# PG4_SHEET2.net
KiCad netlist of a schematic drawn in Altium Designer
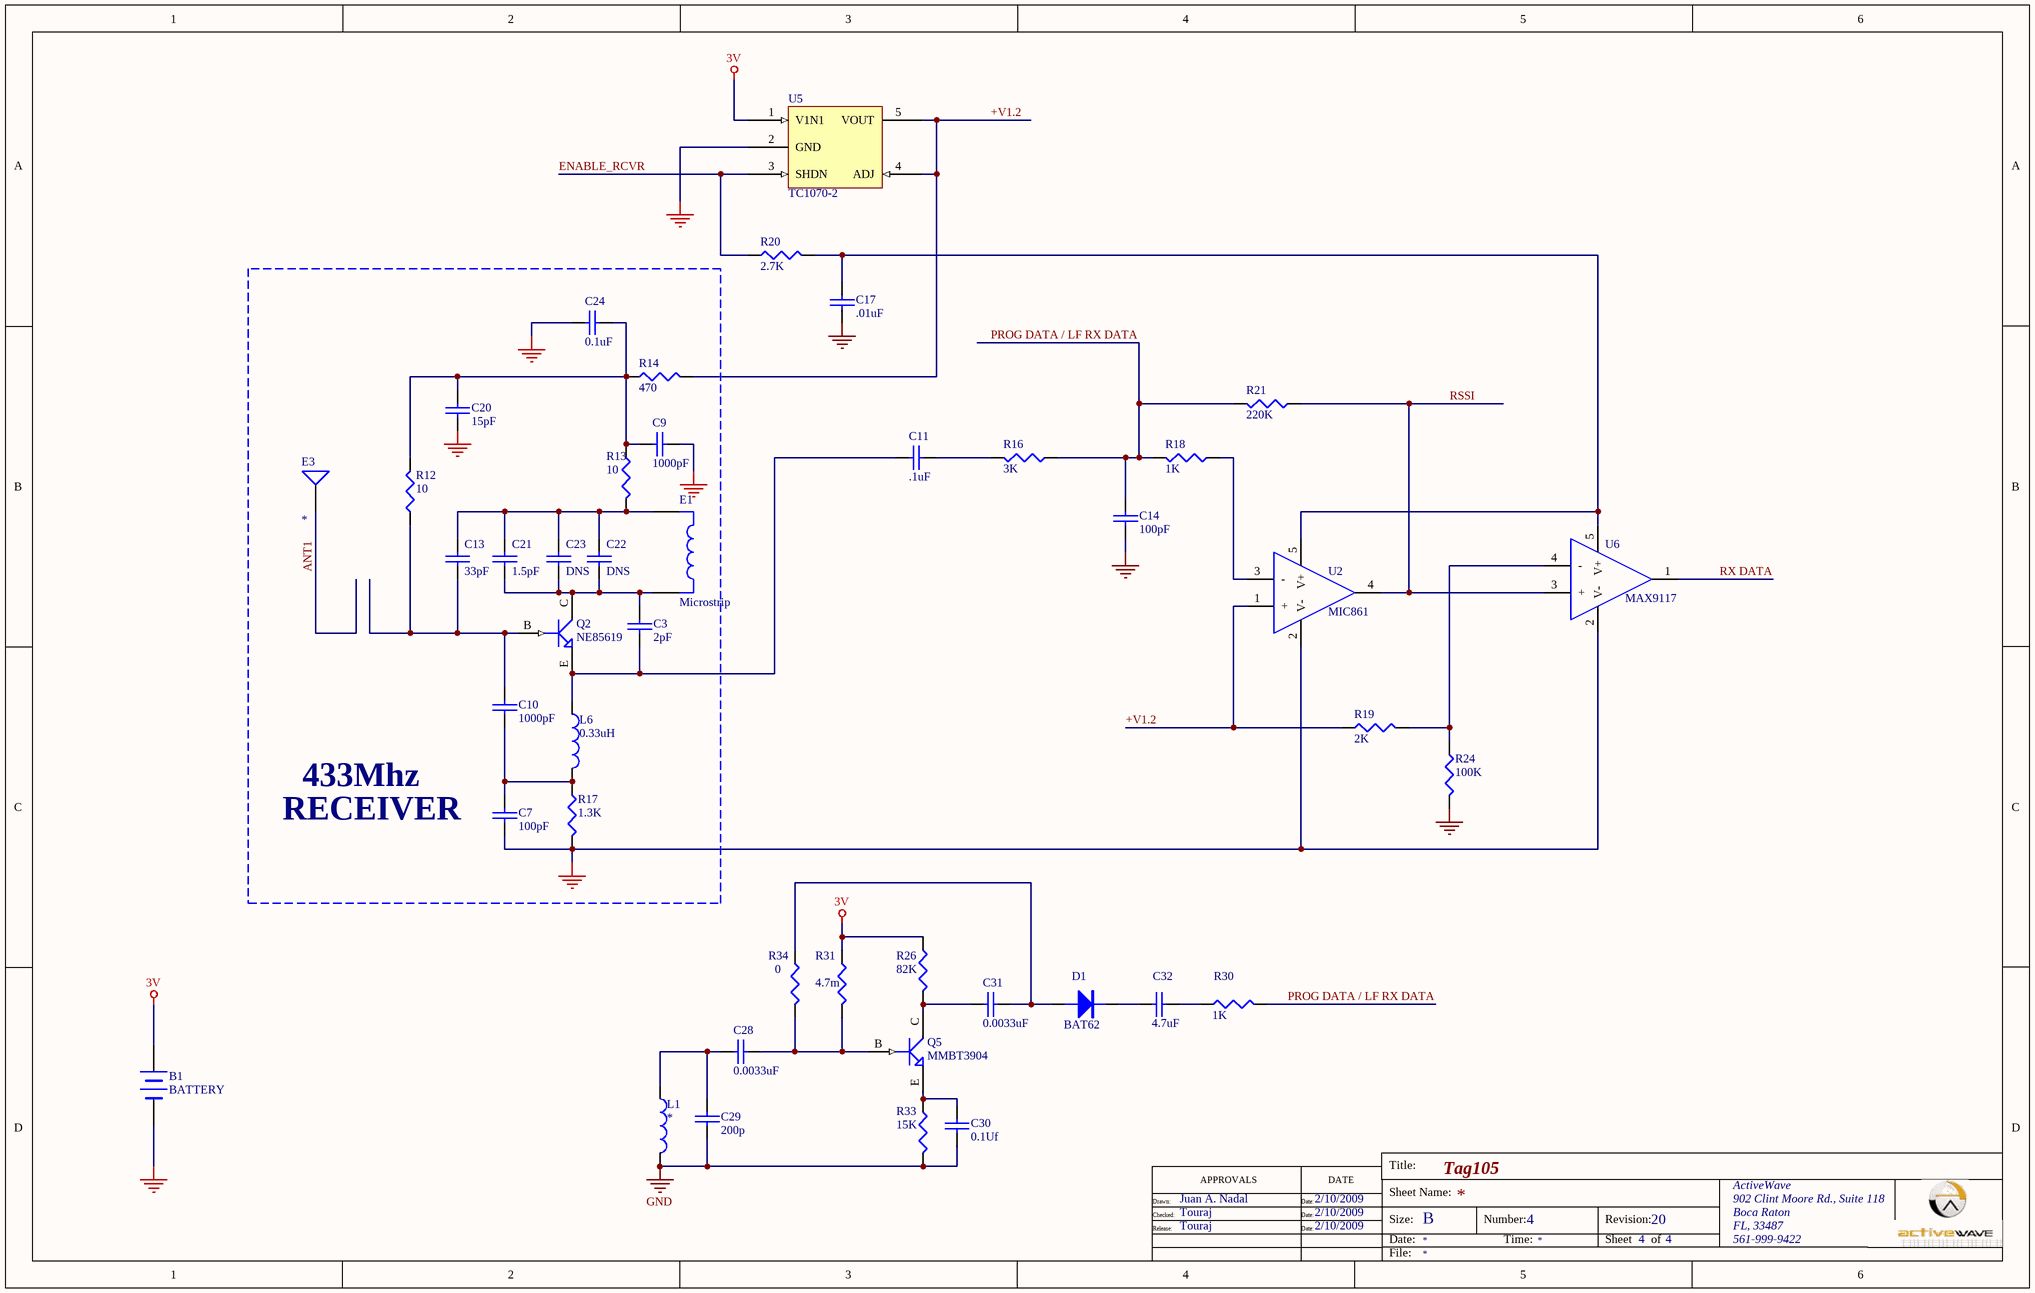
[diagram p0: PG4 SHEET2.schdoc]

(export (version "E")
  (design (tool "Eeschema 10.0.6"))
  (components
    (comp (ref "B1")
      (value "BATTERY")
      (footprint "BATT HOLDER COIN CR2032 CUT")
      (description "Battery")
      (libsource (lib "ActiveWave MasterLib") (part "BATTERY"))
    )
    (comp (ref "C3")
      (value "2pF")
      (footprint "0603")
      (description "Capacitor")
      (libsource (lib "ActiveWave MasterLib") (part "CAP-0603"))
    )
    (comp (ref "C7")
      (value "100pF")
      (footprint "0603")
      (description "Capacitor")
      (libsource (lib "ActiveWave MasterLib") (part "CAP-0603"))
    )
    (comp (ref "C9")
      (value "1000pF")
      (footprint "0603")
      (description "Capacitor")
      (libsource (lib "ActiveWave MasterLib") (part "CAP-0603"))
    )
    (comp (ref "C10")
      (value "1000pF")
      (footprint "0603")
      (description "Capacitor")
      (libsource (lib "ActiveWave MasterLib") (part "CAP-0603"))
    )
    (comp (ref "C11")
      (value ".1uF")
      (footprint "0603")
      (description "Capacitor")
      (libsource (lib "ActiveWave MasterLib") (part "CAP-0603"))
    )
    (comp (ref "C13")
      (value "33pF")
      (footprint "0603")
      (description "Capacitor")
      (libsource (lib "ActiveWave MasterLib") (part "CAP-0603"))
    )
    (comp (ref "C14")
      (value "100pF")
      (footprint "0603")
      (description "Capacitor")
      (libsource (lib "ActiveWave MasterLib") (part "CAP-0603"))
    )
    (comp (ref "C17")
      (value ".01uF")
      (footprint "0603")
      (description "Capacitor")
      (libsource (lib "ActiveWave MasterLib") (part "CAP-0603"))
    )
    (comp (ref "C20")
      (value "15pF")
      (footprint "0603")
      (description "Capacitor")
      (libsource (lib "ActiveWave MasterLib") (part "CAP-0603"))
    )
    (comp (ref "C21")
      (value "1.5pF")
      (footprint "0603")
      (description "Capacitor")
      (libsource (lib "ActiveWave MasterLib") (part "CAP-0603"))
    )
    (comp (ref "C22")
      (value "DNS")
      (footprint "0603")
      (description "Capacitor")
      (libsource (lib "ActiveWave MasterLib") (part "CAP-0603"))
    )
    (comp (ref "C23")
      (value "DNS")
      (footprint "0603")
      (description "Capacitor")
      (libsource (lib "ActiveWave MasterLib") (part "CAP-0603"))
    )
    (comp (ref "C24")
      (value "0.1uF")
      (footprint "0603")
      (description "Capacitor")
      (libsource (lib "ActiveWave MasterLib") (part "CAP-0603"))
    )
    (comp (ref "C28")
      (value "0.0033uF")
      (footprint "0603")
      (description "Capacitor")
      (libsource (lib "ActiveWave MasterLib") (part "CAP-0603"))
    )
    (comp (ref "C29")
      (value "200p")
      (footprint "0603")
      (description "Capacitor")
      (libsource (lib "ActiveWave MasterLib") (part "CAP-0603"))
    )
    (comp (ref "C30")
      (value "0.1Uf")
      (footprint "0603")
      (description "Capacitor")
      (libsource (lib "ActiveWave MasterLib") (part "CAP-0603"))
    )
    (comp (ref "C31")
      (value "0.0033uF")
      (footprint "0603")
      (description "Capacitor")
      (libsource (lib "ActiveWave MasterLib") (part "CAP-0603"))
    )
    (comp (ref "C32")
      (value "4.7uF")
      (footprint "0603")
      (description "Capacitor")
      (libsource (lib "ActiveWave MasterLib") (part "CAP-0603"))
    )
    (comp (ref "D1")
      (value "BAT62")
      (footprint "SMCR_SOD323_V1")
      (libsource (lib "ActiveWave MasterLib") (part "DIODE"))
    )
    (comp (ref "E1")
      (value "Microstrip")
      (footprint "Antenna")
      (fields (field (name "ITEM-DESCRIPTION") "Microstrip"))
      (libsource (lib "ActiveWave MasterLib") (part "ANTENNA"))
    )
    (comp (ref "E3")
      (value "*")
      (footprint "Antenna1")
      (fields (field (name "ALTIUM_VALUE") "*"))
      (libsource (lib "ActiveWave MasterLib") (part "Antenna1"))
    )
    (comp (ref "L1")
      (value "*")
      (footprint "4308RV")
      (fields (field (name "ALTIUM_VALUE") "*"))
      (libsource (lib "ActiveWave MasterLib") (part "INDUCTOR_V1"))
    )
    (comp (ref "L6")
      (value "0.33uH")
      (footprint "0603")
      (libsource (lib "ActiveWave MasterLib") (part "INDUCTOR"))
    )
    (comp (ref "Q2")
      (value "NE85619")
      (footprint "3 PIN ULTRA SUPER MINI MOLD")
      (description "TRANSISTOR NPN 1GHZ SMD")
      (fields (field (name "MANUFACTURER") "??????"))
      (libsource (lib "ActiveWave MasterLib") (part "NE85619"))
    )
    (comp (ref "Q5")
      (value "MMBT3904")
      (footprint "SOT23-EBC")
      (description "NPN SWITCHING TRANSTOR")
      (fields (field (name "MANUFACTURER") "??????"))
      (libsource (lib "ActiveWave MasterLib") (part "MMBT3904"))
    )
    (comp (ref "R12")
      (value "10")
      (footprint "0603")
      (libsource (lib "ActiveWave MasterLib") (part "RES-0603"))
    )
    (comp (ref "R13")
      (value "10")
      (footprint "0603")
      (libsource (lib "ActiveWave MasterLib") (part "RES-0603"))
    )
    (comp (ref "R14")
      (value "470")
      (footprint "0603")
      (libsource (lib "ActiveWave MasterLib") (part "RES-0603"))
    )
    (comp (ref "R16")
      (value "3K")
      (footprint "0603")
      (libsource (lib "ActiveWave MasterLib") (part "RES-0603"))
    )
    (comp (ref "R17")
      (value "1.3K")
      (footprint "0603")
      (libsource (lib "ActiveWave MasterLib") (part "RES-0603"))
    )
    (comp (ref "R18")
      (value "1K")
      (footprint "0603")
      (libsource (lib "ActiveWave MasterLib") (part "RES-0603"))
    )
    (comp (ref "R19")
      (value "2K")
      (footprint "0603")
      (libsource (lib "ActiveWave MasterLib") (part "RES-0603"))
    )
    (comp (ref "R20")
      (value "2.7K")
      (footprint "0603")
      (libsource (lib "ActiveWave MasterLib") (part "RES-0603"))
    )
    (comp (ref "R21")
      (value "220K")
      (footprint "0603")
      (libsource (lib "ActiveWave MasterLib") (part "RES-0603"))
    )
    (comp (ref "R24")
      (value "100K")
      (footprint "0603")
      (libsource (lib "ActiveWave MasterLib") (part "RES-0603"))
    )
    (comp (ref "R26")
      (value "82K")
      (footprint "0603")
      (libsource (lib "ActiveWave MasterLib") (part "RES-0603"))
    )
    (comp (ref "R30")
      (value "1K")
      (footprint "0603")
      (libsource (lib "ActiveWave MasterLib") (part "RES-0603"))
    )
    (comp (ref "R31")
      (value "4.7m")
      (footprint "0603")
      (libsource (lib "ActiveWave MasterLib") (part "RES-0603"))
    )
    (comp (ref "R33")
      (value "15K")
      (footprint "0603")
      (libsource (lib "ActiveWave MasterLib") (part "RES-0603"))
    )
    (comp (ref "R34")
      (value "0")
      (footprint "0603")
      (libsource (lib "ActiveWave MasterLib") (part "RES-0603"))
    )
    (comp (ref "U2")
      (value "MIC861")
      (footprint "SC70")
      (description "Ultra Low Power Op Amp")
      (fields (field (name "MANUFACTURER") "MICREL"))
      (libsource (lib "ActiveWave MasterLib") (part "MIC861BC5"))
    )
    (comp (ref "U5")
      (value "TC1070-2")
      (footprint "SOT23-5A")
      (description "Adjustable CMOS LDOs with Shutdown")
      (fields (field (name "MANUFACTURER") "Microchip Technology"))
      (libsource (lib "ActiveWave MasterLib") (part "TC1070-2"))
    )
    (comp (ref "U6")
      (value "MAX9117")
      (footprint "SC70")
      (description "MAX9117 Comparators")
      (fields (field (name "MANUFACTURER") "MAXIM"))
      (libsource (lib "ActiveWave MasterLib") (part "COMPARATOR MAX9117"))
    )
  )
  (nets
    (net (code "1") (name "/+V1.2") (class "Default")
      (node (ref "R14") (pin "2") (pinfunction "2_2") (pintype "passive"))
      (node (ref "R19") (pin "1") (pinfunction "1_1") (pintype "passive"))
      (node (ref "U2") (pin "1") (pinfunction "+_1") (pintype "passive"))
      (node (ref "U5") (pin "4") (pinfunction "ADJ_4") (pintype "input"))
      (node (ref "U5") (pin "5") (pinfunction "VOUT_5") (pintype "power_in"))
    )
    (net (code "2") (name "/ANT1") (class "Default")
      (node (ref "E3") (pin "1") (pinfunction "1_1") (pintype "passive"))
    )
    (net (code "3") (name "/ENABLE_RCVR") (class "Default")
      (node (ref "R20") (pin "1") (pinfunction "1_1") (pintype "passive"))
      (node (ref "U5") (pin "3") (pinfunction "SHDN_3") (pintype "input"))
    )
    (net (code "4") (name "/PROG DATA {slash} LF RX DATA") (class "Default")
      (node (ref "C14") (pin "2") (pinfunction "2_2") (pintype "passive"))
      (node (ref "R16") (pin "1") (pinfunction "1_1") (pintype "passive"))
      (node (ref "R18") (pin "2") (pinfunction "2_2") (pintype "passive"))
      (node (ref "R21") (pin "2") (pinfunction "2_2") (pintype "passive"))
      (node (ref "R30") (pin "2") (pinfunction "2_2") (pintype "passive"))
    )
    (net (code "5") (name "/RSSI") (class "Default")
      (node (ref "R21") (pin "1") (pinfunction "1_1") (pintype "passive"))
      (node (ref "U2") (pin "4") (pinfunction "OUT_4") (pintype "passive"))
      (node (ref "U6") (pin "3") (pinfunction "+_3") (pintype "passive"))
    )
    (net (code "6") (name "/RX DATA") (class "Default")
      (node (ref "U6") (pin "1") (pinfunction "OUT_1") (pintype "passive"))
    )
    (net (code "7") (name "3V") (class "Default")
      (node (ref "B1") (pin "2") (pinfunction "+_2") (pintype "passive"))
      (node (ref "R26") (pin "1") (pinfunction "1_1") (pintype "passive"))
      (node (ref "R31") (pin "1") (pinfunction "1_1") (pintype "passive"))
      (node (ref "U5") (pin "1") (pinfunction "V1N1_1") (pintype "input"))
    )
    (net (code "8") (name "GND") (class "Default")
      (node (ref "B1") (pin "1") (pinfunction "-_1") (pintype "passive"))
      (node (ref "C14") (pin "1") (pinfunction "1_1") (pintype "passive"))
      (node (ref "C17") (pin "2") (pinfunction "2_2") (pintype "passive"))
      (node (ref "C20") (pin "2") (pinfunction "2_2") (pintype "passive"))
      (node (ref "C24") (pin "2") (pinfunction "2_2") (pintype "passive"))
      (node (ref "C29") (pin "1") (pinfunction "1_1") (pintype "passive"))
      (node (ref "C30") (pin "1") (pinfunction "1_1") (pintype "passive"))
      (node (ref "C7") (pin "2") (pinfunction "2_2") (pintype "passive"))
      (node (ref "C9") (pin "2") (pinfunction "2_2") (pintype "passive"))
      (node (ref "L1") (pin "2") (pinfunction "2_2") (pintype "passive"))
      (node (ref "R17") (pin "2") (pinfunction "2_2") (pintype "passive"))
      (node (ref "R24") (pin "2") (pinfunction "2_2") (pintype "passive"))
      (node (ref "R33") (pin "2") (pinfunction "2_2") (pintype "passive"))
      (node (ref "U2") (pin "2") (pinfunction "V-_2") (pintype "passive"))
      (node (ref "U5") (pin "2") (pinfunction "GND_2") (pintype "power_in"))
      (node (ref "U6") (pin "2") (pinfunction "V-_2") (pintype "passive"))
    )
    (net (code "9") (name "Net-(C10-Pad1)") (class "Default")
      (node (ref "C10") (pin "1") (pinfunction "1_1") (pintype "passive"))
      (node (ref "C13") (pin "2") (pinfunction "2_2") (pintype "passive"))
      (node (ref "Q2") (pin "B") (pinfunction "B_B") (pintype "input"))
      (node (ref "R12") (pin "1") (pinfunction "1_1") (pintype "passive"))
    )
    (net (code "10") (name "Net-(C10-Pad2)") (class "Default")
      (node (ref "C10") (pin "2") (pinfunction "2_2") (pintype "passive"))
      (node (ref "C7") (pin "1") (pinfunction "1_1") (pintype "passive"))
      (node (ref "L6") (pin "2") (pinfunction "2_2") (pintype "passive"))
      (node (ref "R17") (pin "1") (pinfunction "1_1") (pintype "passive"))
    )
    (net (code "11") (name "Net-(C11-Pad1)") (class "Default")
      (node (ref "C11") (pin "1") (pinfunction "1_1") (pintype "passive"))
      (node (ref "C3") (pin "2") (pinfunction "2_2") (pintype "passive"))
      (node (ref "L6") (pin "1") (pinfunction "1_1") (pintype "passive"))
      (node (ref "Q2") (pin "E") (pinfunction "E_E") (pintype "passive"))
    )
    (net (code "12") (name "Net-(C11-Pad2)") (class "Default")
      (node (ref "C11") (pin "2") (pinfunction "2_2") (pintype "passive"))
      (node (ref "R16") (pin "2") (pinfunction "2_2") (pintype "passive"))
    )
    (net (code "13") (name "Net-(C13-Pad1)") (class "Default")
      (node (ref "C13") (pin "1") (pinfunction "1_1") (pintype "passive"))
      (node (ref "C21") (pin "1") (pinfunction "1_1") (pintype "passive"))
      (node (ref "C22") (pin "1") (pinfunction "1_1") (pintype "passive"))
      (node (ref "C23") (pin "1") (pinfunction "1_1") (pintype "passive"))
      (node (ref "E1") (pin "2") (pinfunction "2_2") (pintype "passive"))
      (node (ref "R13") (pin "2") (pinfunction "2_2") (pintype "passive"))
    )
    (net (code "14") (name "Net-(C20-Pad1)") (class "Default")
      (node (ref "C20") (pin "1") (pinfunction "1_1") (pintype "passive"))
      (node (ref "C24") (pin "1") (pinfunction "1_1") (pintype "passive"))
      (node (ref "C9") (pin "1") (pinfunction "1_1") (pintype "passive"))
      (node (ref "R12") (pin "2") (pinfunction "2_2") (pintype "passive"))
      (node (ref "R13") (pin "1") (pinfunction "1_1") (pintype "passive"))
      (node (ref "R14") (pin "1") (pinfunction "1_1") (pintype "passive"))
    )
    (net (code "15") (name "Net-(C21-Pad2)") (class "Default")
      (node (ref "C21") (pin "2") (pinfunction "2_2") (pintype "passive"))
      (node (ref "C22") (pin "2") (pinfunction "2_2") (pintype "passive"))
      (node (ref "C23") (pin "2") (pinfunction "2_2") (pintype "passive"))
      (node (ref "C3") (pin "1") (pinfunction "1_1") (pintype "passive"))
      (node (ref "E1") (pin "1") (pinfunction "1_1") (pintype "passive"))
      (node (ref "Q2") (pin "C") (pinfunction "C_C") (pintype "passive"))
    )
    (net (code "16") (name "Net-(C28-Pad1)") (class "Default")
      (node (ref "C28") (pin "1") (pinfunction "1_1") (pintype "passive"))
      (node (ref "C29") (pin "2") (pinfunction "2_2") (pintype "passive"))
      (node (ref "L1") (pin "1") (pinfunction "1_1") (pintype "passive"))
    )
    (net (code "17") (name "Net-(C31-Pad2)") (class "Default")
      (node (ref "C31") (pin "2") (pinfunction "2_2") (pintype "passive"))
      (node (ref "D1") (pin "A") (pinfunction "A_A") (pintype "passive"))
      (node (ref "R34") (pin "1") (pinfunction "1_1") (pintype "passive"))
    )
    (net (code "18") (name "Net-(C32-Pad1)") (class "Default")
      (node (ref "C32") (pin "1") (pinfunction "1_1") (pintype "passive"))
      (node (ref "D1") (pin "K") (pinfunction "K_K") (pintype "passive"))
    )
    (net (code "19") (name "Net-(C32-Pad2)") (class "Default")
      (node (ref "C32") (pin "2") (pinfunction "2_2") (pintype "passive"))
      (node (ref "R30") (pin "1") (pinfunction "1_1") (pintype "passive"))
    )
    (net (code "20") (name "Net-(Q5-1)") (class "Default")
      (node (ref "C28") (pin "2") (pinfunction "2_2") (pintype "passive"))
      (node (ref "Q5") (pin "B") (pinfunction "1_B") (pintype "input"))
      (node (ref "R31") (pin "2") (pinfunction "2_2") (pintype "passive"))
      (node (ref "R34") (pin "2") (pinfunction "2_2") (pintype "passive"))
    )
    (net (code "21") (name "Net-(Q5-2)") (class "Default")
      (node (ref "C30") (pin "2") (pinfunction "2_2") (pintype "passive"))
      (node (ref "Q5") (pin "E") (pinfunction "2_E") (pintype "passive"))
      (node (ref "R33") (pin "1") (pinfunction "1_1") (pintype "passive"))
    )
    (net (code "22") (name "Net-(Q5-3)") (class "Default")
      (node (ref "C31") (pin "1") (pinfunction "1_1") (pintype "passive"))
      (node (ref "Q5") (pin "C") (pinfunction "3_C") (pintype "passive"))
      (node (ref "R26") (pin "2") (pinfunction "2_2") (pintype "passive"))
    )
    (net (code "23") (name "Net-(U2--)") (class "Default")
      (node (ref "R18") (pin "1") (pinfunction "1_1") (pintype "passive"))
      (node (ref "U2") (pin "3") (pinfunction "-_3") (pintype "passive"))
    )
    (net (code "24") (name "Net-(U2-V+)") (class "Default")
      (node (ref "C17") (pin "1") (pinfunction "1_1") (pintype "passive"))
      (node (ref "R20") (pin "2") (pinfunction "2_2") (pintype "passive"))
      (node (ref "U2") (pin "5") (pinfunction "V+_5") (pintype "passive"))
      (node (ref "U6") (pin "5") (pinfunction "V+_5") (pintype "passive"))
    )
    (net (code "25") (name "Net-(U6--)") (class "Default")
      (node (ref "R19") (pin "2") (pinfunction "2_2") (pintype "passive"))
      (node (ref "R24") (pin "1") (pinfunction "1_1") (pintype "passive"))
      (node (ref "U6") (pin "4") (pinfunction "-_4") (pintype "passive"))
    )
  )
)
